# Motor_Control_no_mask.net
KiCad netlist of a schematic drawn in EAGLE
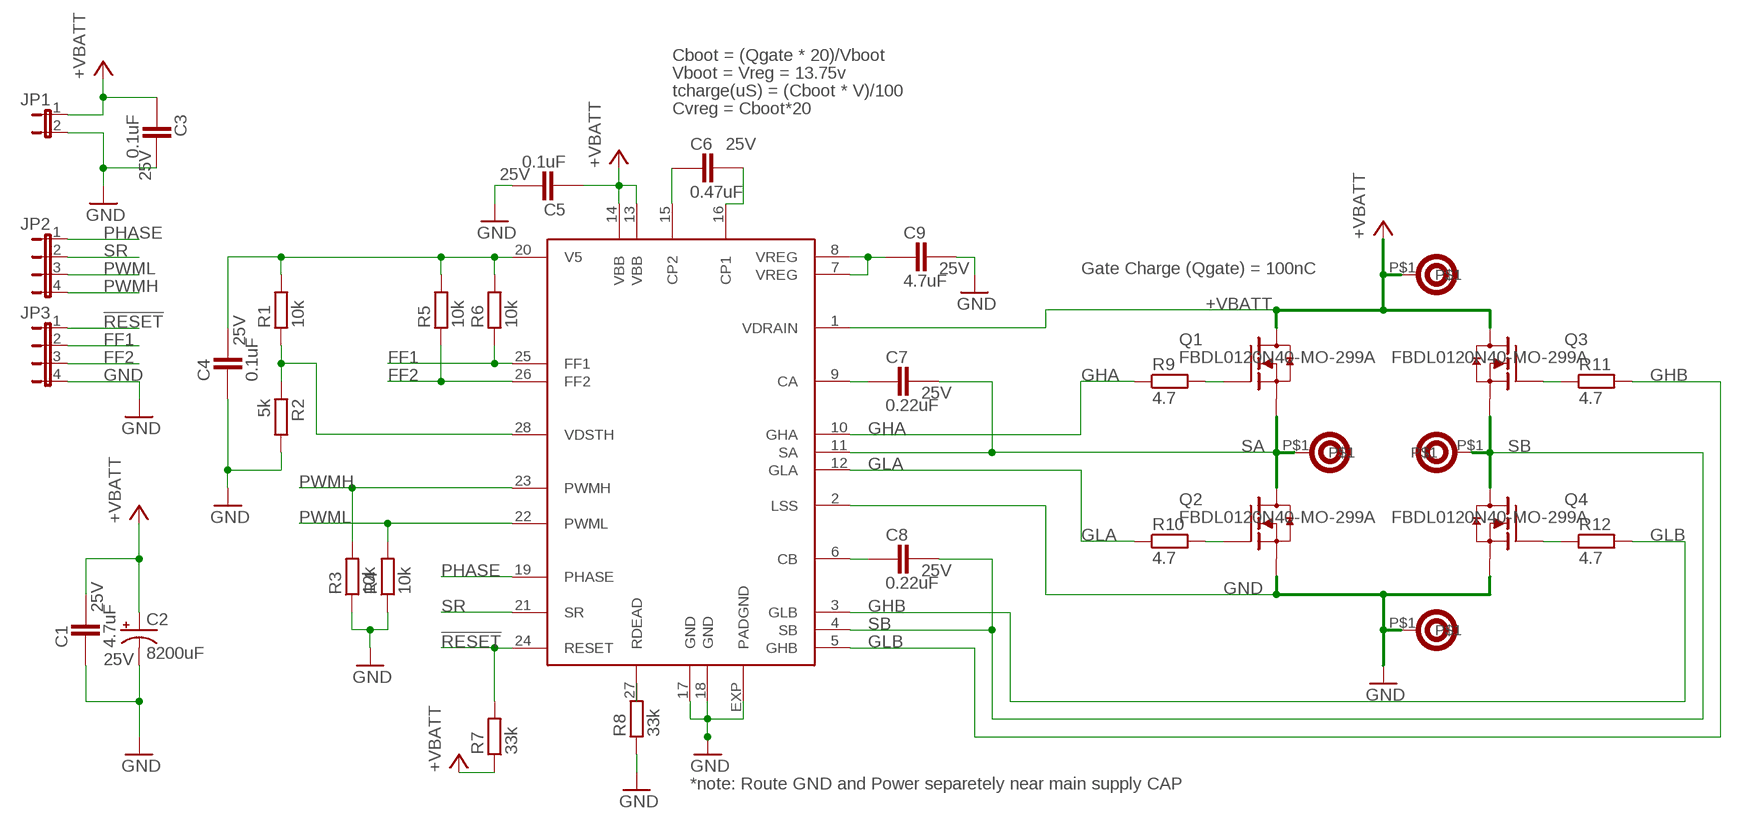
[diagram p0: schematic, sheet 1]

(export (version "E")
  (design (tool "Eeschema 10.0.6"))
  (components
    (comp (ref "C1")
      (value "4.7uF")
      (footprint "eagle-import:CAPC1608X92N")
      (fields (field (name "VOLTAGE") "25V"))
      (libsource (lib "eagle-import") (part "CAPACITOR_0603"))
    )
    (comp (ref "C2")
      (value "8200uF")
      (footprint "eagle-import:CAP-10-22")
      (fields
        (field (name "MANUFACTURER") "Panasonic")
        (field (name "MANUFACTURER_PART_NUMBER") "ECO-S1EA822BA")
        (field (name "VOLTAGE") "25V")
      )
      (libsource (lib "eagle-import") (part "CPOL-US-PTH-10-22"))
    )
    (comp (ref "C3")
      (value "0.1uF")
      (footprint "eagle-import:CAPC1608X92N")
      (fields (field (name "VOLTAGE") "25V"))
      (libsource (lib "eagle-import") (part "CAPACITOR_0603"))
    )
    (comp (ref "C4")
      (value "0.1uF")
      (footprint "eagle-import:CAPC_0603_LONG")
      (fields (field (name "VOLTAGE") "25V"))
      (libsource (lib "eagle-import") (part "CAPACITOR_0603L"))
    )
    (comp (ref "C5")
      (value "0.1uF")
      (footprint "eagle-import:CAPC1608X92N")
      (fields (field (name "VOLTAGE") "25V"))
      (libsource (lib "eagle-import") (part "CAPACITOR_0603"))
    )
    (comp (ref "C6")
      (value "0.47uF")
      (footprint "eagle-import:CAPC1608X92N")
      (fields (field (name "VOLTAGE") "25V"))
      (libsource (lib "eagle-import") (part "CAPACITOR_0603"))
    )
    (comp (ref "C7")
      (value "0.22uF")
      (footprint "eagle-import:CAPC_0603_LONG")
      (fields (field (name "VOLTAGE") "25V"))
      (libsource (lib "eagle-import") (part "CAPACITOR_0603L"))
    )
    (comp (ref "C8")
      (value "0.22uF")
      (footprint "eagle-import:CAPC_0603_LONG")
      (fields (field (name "VOLTAGE") "25V"))
      (libsource (lib "eagle-import") (part "CAPACITOR_0603L"))
    )
    (comp (ref "C9")
      (value "4.7uF")
      (footprint "eagle-import:CAPC1608X92N")
      (fields (field (name "VOLTAGE") "25V"))
      (libsource (lib "eagle-import") (part "CAPACITOR_0603"))
    )
    (comp (ref "J1")
      (value "63971-1-QC_TAB-RA")
      (footprint "eagle-import:QUICK_CONN_TAB-RA")
      (fields
        (field (name "MANUFACTURER") "TE Connectivity")
        (field (name "MANUFACTURER_PART_NUMBER") "63971-1")
      )
      (libsource (lib "eagle-import") (part "63971-1-QC_TAB-RA"))
    )
    (comp (ref "J2")
      (value "63971-1-QC_TAB-RA")
      (footprint "eagle-import:QUICK_CONN_TAB-RA")
      (fields
        (field (name "MANUFACTURER") "TE Connectivity")
        (field (name "MANUFACTURER_PART_NUMBER") "63971-1")
      )
      (libsource (lib "eagle-import") (part "63971-1-QC_TAB-RA"))
    )
    (comp (ref "J3")
      (value "63971-1-QC_TAB-RA")
      (footprint "eagle-import:QUICK_CONN_TAB-RA")
      (fields
        (field (name "MANUFACTURER") "TE Connectivity")
        (field (name "MANUFACTURER_PART_NUMBER") "63971-1")
      )
      (libsource (lib "eagle-import") (part "63971-1-QC_TAB-RA"))
    )
    (comp (ref "J4")
      (value "63971-1-QC_TAB-RA")
      (footprint "eagle-import:QUICK_CONN_TAB-RA")
      (fields
        (field (name "MANUFACTURER") "TE Connectivity")
        (field (name "MANUFACTURER_PART_NUMBER") "63971-1")
      )
      (libsource (lib "eagle-import") (part "63971-1-QC_TAB-RA"))
    )
    (comp (ref "JP1")
      (value "JP1E")
      (footprint "eagle-import:JP1")
      (libsource (lib "eagle-import") (part "JP1E"))
    )
    (comp (ref "JP2")
      (value "JP4E")
      (footprint "eagle-import:JP4")
      (libsource (lib "eagle-import") (part "JP4E"))
    )
    (comp (ref "JP3")
      (value "JP4E")
      (footprint "eagle-import:JP4")
      (libsource (lib "eagle-import") (part "JP4E"))
    )
    (comp (ref "Q1")
      (value "FBDL0120N40-MO-299A")
      (footprint "eagle-import:MO-299")
      (fields
        (field (name "MANUFACTURER") "Fairchild")
        (field (name "MANUFACTURER_PART_NUMBER") "FDBL0120N40")
      )
      (libsource (lib "eagle-import") (part "FBDL0120N40-MO-299A"))
    )
    (comp (ref "Q2")
      (value "FBDL0120N40-MO-299A")
      (footprint "eagle-import:MO-299")
      (fields
        (field (name "MANUFACTURER") "Fairchild")
        (field (name "MANUFACTURER_PART_NUMBER") "FDBL0120N40")
      )
      (libsource (lib "eagle-import") (part "FBDL0120N40-MO-299A"))
    )
    (comp (ref "Q3")
      (value "FBDL0120N40-MO-299A")
      (footprint "eagle-import:MO-299")
      (fields
        (field (name "MANUFACTURER") "Fairchild")
        (field (name "MANUFACTURER_PART_NUMBER") "FDBL0120N40")
      )
      (libsource (lib "eagle-import") (part "FBDL0120N40-MO-299A"))
    )
    (comp (ref "Q4")
      (value "FBDL0120N40-MO-299A")
      (footprint "eagle-import:MO-299")
      (fields
        (field (name "MANUFACTURER") "Fairchild")
        (field (name "MANUFACTURER_PART_NUMBER") "FDBL0120N40")
      )
      (libsource (lib "eagle-import") (part "FBDL0120N40-MO-299A"))
    )
    (comp (ref "R1")
      (value "10k")
      (footprint "eagle-import:RESC1608X55N")
      (libsource (lib "eagle-import") (part "RESISTOR_0603"))
    )
    (comp (ref "R2")
      (value "5k")
      (footprint "eagle-import:RESC1608X55N")
      (libsource (lib "eagle-import") (part "RESISTOR_0603"))
    )
    (comp (ref "R3")
      (value "10k")
      (footprint "eagle-import:RESC1608X55N")
      (libsource (lib "eagle-import") (part "RESISTOR_0603"))
    )
    (comp (ref "R4")
      (value "10k")
      (footprint "eagle-import:RESC1608X55N")
      (libsource (lib "eagle-import") (part "RESISTOR_0603"))
    )
    (comp (ref "R5")
      (value "10k")
      (footprint "eagle-import:RESC1608X55N")
      (libsource (lib "eagle-import") (part "RESISTOR_0603"))
    )
    (comp (ref "R6")
      (value "10k")
      (footprint "eagle-import:RESC1608X55N")
      (libsource (lib "eagle-import") (part "RESISTOR_0603"))
    )
    (comp (ref "R7")
      (value "33k")
      (footprint "eagle-import:RESC1608X55N")
      (libsource (lib "eagle-import") (part "RESISTOR_0603"))
    )
    (comp (ref "R8")
      (value "33k")
      (footprint "eagle-import:RESC1608X55N")
      (libsource (lib "eagle-import") (part "RESISTOR_0603"))
    )
    (comp (ref "R9")
      (value "4.7")
      (footprint "eagle-import:RESC1608X55N")
      (libsource (lib "eagle-import") (part "RESISTOR_0603"))
    )
    (comp (ref "R10")
      (value "4.7")
      (footprint "eagle-import:RESC1608X55N")
      (libsource (lib "eagle-import") (part "RESISTOR_0603"))
    )
    (comp (ref "R11")
      (value "4.7")
      (footprint "eagle-import:RESC1608X55N")
      (libsource (lib "eagle-import") (part "RESISTOR_0603"))
    )
    (comp (ref "R12")
      (value "4.7")
      (footprint "eagle-import:RESC1608X55N")
      (libsource (lib "eagle-import") (part "RESISTOR_0603"))
    )
    (comp (ref "U1")
      (value "A3941-TSSOP28-LP")
      (footprint "eagle-import:TSSOP28-LP")
      (fields
        (field (name "MANUFACTURER") "Allegro MicroSystems LLC")
        (field (name "MANUFACTURER_PART_NUMBER") "A3941")
      )
      (libsource (lib "eagle-import") (part "A3941-TSSOP28-LP"))
    )
  )
  (nets
    (net (code "1") (name "+VBATT") (class "Default")
      (node (ref "C1") (pin "2") (pinfunction "2_2") (pintype "passive"))
      (node (ref "C2") (pin "+") (pinfunction "+_+") (pintype "passive"))
      (node (ref "C3") (pin "1") (pinfunction "1_1") (pintype "passive"))
      (node (ref "C5") (pin "1") (pinfunction "1_1") (pintype "passive"))
      (node (ref "J2") (pin "P$1") (pinfunction "P$1_P$1") (pintype "bidirectional"))
      (node (ref "JP1") (pin "1") (pinfunction "1_1") (pintype "passive"))
      (node (ref "Q1") (pin "P$9") (pinfunction "D_P$9") (pintype "passive"))
      (node (ref "Q3") (pin "P$9") (pinfunction "D_P$9") (pintype "passive"))
      (node (ref "R7") (pin "1") (pinfunction "1_1") (pintype "passive"))
      (node (ref "U1") (pin "1") (pinfunction "VDRAIN_1") (pintype "bidirectional"))
      (node (ref "U1") (pin "13") (pinfunction "VBB_13") (pintype "bidirectional"))
      (node (ref "U1") (pin "14") (pinfunction "VBB_14") (pintype "bidirectional"))
    )
    (net (code "2") (name "/FF1") (class "Default")
      (node (ref "JP3") (pin "2") (pinfunction "2_2") (pintype "passive"))
      (node (ref "R6") (pin "1") (pinfunction "1_1") (pintype "passive"))
      (node (ref "U1") (pin "25") (pinfunction "FF1_25") (pintype "output"))
    )
    (net (code "3") (name "/FF2") (class "Default")
      (node (ref "JP3") (pin "3") (pinfunction "3_3") (pintype "passive"))
      (node (ref "R5") (pin "1") (pinfunction "1_1") (pintype "passive"))
      (node (ref "U1") (pin "26") (pinfunction "FF2_26") (pintype "output"))
    )
    (net (code "4") (name "/GHA") (class "Default")
      (node (ref "R9") (pin "1") (pinfunction "1_1") (pintype "passive"))
      (node (ref "U1") (pin "10") (pinfunction "GHA_10") (pintype "output"))
    )
    (net (code "5") (name "/GHB") (class "Default")
      (node (ref "R11") (pin "2") (pinfunction "2_2") (pintype "passive"))
      (node (ref "U1") (pin "5") (pinfunction "GHB_5") (pintype "output"))
    )
    (net (code "6") (name "/GLA") (class "Default")
      (node (ref "R10") (pin "1") (pinfunction "1_1") (pintype "passive"))
      (node (ref "U1") (pin "12") (pinfunction "GLA_12") (pintype "output"))
    )
    (net (code "7") (name "/GLB") (class "Default")
      (node (ref "R12") (pin "2") (pinfunction "2_2") (pintype "passive"))
      (node (ref "U1") (pin "3") (pinfunction "GLB_3") (pintype "output"))
    )
    (net (code "8") (name "/PHASE") (class "Default")
      (node (ref "JP2") (pin "1") (pinfunction "1_1") (pintype "passive"))
      (node (ref "U1") (pin "19") (pinfunction "PHASE_19") (pintype "input"))
    )
    (net (code "9") (name "/PWMH") (class "Default")
      (node (ref "JP2") (pin "4") (pinfunction "4_4") (pintype "passive"))
      (node (ref "R3") (pin "2") (pinfunction "2_2") (pintype "passive"))
      (node (ref "U1") (pin "23") (pinfunction "PWMH_23") (pintype "input"))
    )
    (net (code "10") (name "/PWML") (class "Default")
      (node (ref "JP2") (pin "3") (pinfunction "3_3") (pintype "passive"))
      (node (ref "R4") (pin "2") (pinfunction "2_2") (pintype "passive"))
      (node (ref "U1") (pin "22") (pinfunction "PWML_22") (pintype "input"))
    )
    (net (code "11") (name "/SA") (class "Default")
      (node (ref "C7") (pin "2") (pinfunction "2_2") (pintype "passive"))
      (node (ref "J1") (pin "P$1") (pinfunction "P$1_P$1") (pintype "bidirectional"))
      (node (ref "Q1") (pin "P$2") (pinfunction "S_P$2") (pintype "passive"))
      (node (ref "Q1") (pin "P$3") (pinfunction "S_P$3") (pintype "passive"))
      (node (ref "Q1") (pin "P$4") (pinfunction "S_P$4") (pintype "passive"))
      (node (ref "Q1") (pin "P$5") (pinfunction "S_P$5") (pintype "passive"))
      (node (ref "Q1") (pin "P$6") (pinfunction "S_P$6") (pintype "passive"))
      (node (ref "Q1") (pin "P$7") (pinfunction "S_P$7") (pintype "passive"))
      (node (ref "Q1") (pin "P$8") (pinfunction "S_P$8") (pintype "passive"))
      (node (ref "Q2") (pin "P$9") (pinfunction "D_P$9") (pintype "passive"))
      (node (ref "U1") (pin "11") (pinfunction "SA_11") (pintype "bidirectional"))
    )
    (net (code "12") (name "/SB") (class "Default")
      (node (ref "C8") (pin "2") (pinfunction "2_2") (pintype "passive"))
      (node (ref "J3") (pin "P$1") (pinfunction "P$1_P$1") (pintype "bidirectional"))
      (node (ref "Q3") (pin "P$2") (pinfunction "S_P$2") (pintype "passive"))
      (node (ref "Q3") (pin "P$3") (pinfunction "S_P$3") (pintype "passive"))
      (node (ref "Q3") (pin "P$4") (pinfunction "S_P$4") (pintype "passive"))
      (node (ref "Q3") (pin "P$5") (pinfunction "S_P$5") (pintype "passive"))
      (node (ref "Q3") (pin "P$6") (pinfunction "S_P$6") (pintype "passive"))
      (node (ref "Q3") (pin "P$7") (pinfunction "S_P$7") (pintype "passive"))
      (node (ref "Q3") (pin "P$8") (pinfunction "S_P$8") (pintype "passive"))
      (node (ref "Q4") (pin "P$9") (pinfunction "D_P$9") (pintype "passive"))
      (node (ref "U1") (pin "4") (pinfunction "SB_4") (pintype "bidirectional"))
    )
    (net (code "13") (name "/SR") (class "Default")
      (node (ref "JP2") (pin "2") (pinfunction "2_2") (pintype "passive"))
      (node (ref "U1") (pin "21") (pinfunction "SR_21") (pintype "input"))
    )
    (net (code "14") (name "/~{RESET}") (class "Default")
      (node (ref "JP3") (pin "1") (pinfunction "1_1") (pintype "passive"))
      (node (ref "R7") (pin "2") (pinfunction "2_2") (pintype "passive"))
      (node (ref "U1") (pin "24") (pinfunction "RESET_24") (pintype "input"))
    )
    (net (code "15") (name "GND") (class "Default")
      (node (ref "C1") (pin "1") (pinfunction "1_1") (pintype "passive"))
      (node (ref "C2") (pin "-") (pinfunction "-_-") (pintype "passive"))
      (node (ref "C3") (pin "2") (pinfunction "2_2") (pintype "passive"))
      (node (ref "C4") (pin "1") (pinfunction "1_1") (pintype "passive"))
      (node (ref "C5") (pin "2") (pinfunction "2_2") (pintype "passive"))
      (node (ref "C9") (pin "2") (pinfunction "2_2") (pintype "passive"))
      (node (ref "J4") (pin "P$1") (pinfunction "P$1_P$1") (pintype "bidirectional"))
      (node (ref "JP1") (pin "2") (pinfunction "2_2") (pintype "passive"))
      (node (ref "JP3") (pin "4") (pinfunction "4_4") (pintype "passive"))
      (node (ref "Q2") (pin "P$2") (pinfunction "S_P$2") (pintype "passive"))
      (node (ref "Q2") (pin "P$3") (pinfunction "S_P$3") (pintype "passive"))
      (node (ref "Q2") (pin "P$4") (pinfunction "S_P$4") (pintype "passive"))
      (node (ref "Q2") (pin "P$5") (pinfunction "S_P$5") (pintype "passive"))
      (node (ref "Q2") (pin "P$6") (pinfunction "S_P$6") (pintype "passive"))
      (node (ref "Q2") (pin "P$7") (pinfunction "S_P$7") (pintype "passive"))
      (node (ref "Q2") (pin "P$8") (pinfunction "S_P$8") (pintype "passive"))
      (node (ref "Q4") (pin "P$2") (pinfunction "S_P$2") (pintype "passive"))
      (node (ref "Q4") (pin "P$3") (pinfunction "S_P$3") (pintype "passive"))
      (node (ref "Q4") (pin "P$4") (pinfunction "S_P$4") (pintype "passive"))
      (node (ref "Q4") (pin "P$5") (pinfunction "S_P$5") (pintype "passive"))
      (node (ref "Q4") (pin "P$6") (pinfunction "S_P$6") (pintype "passive"))
      (node (ref "Q4") (pin "P$7") (pinfunction "S_P$7") (pintype "passive"))
      (node (ref "Q4") (pin "P$8") (pinfunction "S_P$8") (pintype "passive"))
      (node (ref "R2") (pin "2") (pinfunction "2_2") (pintype "passive"))
      (node (ref "R3") (pin "1") (pinfunction "1_1") (pintype "passive"))
      (node (ref "R4") (pin "1") (pinfunction "1_1") (pintype "passive"))
      (node (ref "R8") (pin "1") (pinfunction "1_1") (pintype "passive"))
      (node (ref "U1") (pin "17") (pinfunction "GND_17") (pintype "bidirectional"))
      (node (ref "U1") (pin "18") (pinfunction "GND_18") (pintype "bidirectional"))
      (node (ref "U1") (pin "2") (pinfunction "LSS_2") (pintype "bidirectional"))
      (node (ref "U1") (pin "EXP") (pinfunction "PADGND_EXP") (pintype "bidirectional"))
    )
    (net (code "16") (name "Net-(C9-Pad1)") (class "Default")
      (node (ref "C9") (pin "1") (pinfunction "1_1") (pintype "passive"))
      (node (ref "U1") (pin "7") (pinfunction "VREG_7") (pintype "bidirectional"))
      (node (ref "U1") (pin "8") (pinfunction "VREG_8") (pintype "bidirectional"))
    )
    (net (code "17") (name "Net-(Q1-G)") (class "Default")
      (node (ref "Q1") (pin "P$1") (pinfunction "G_P$1") (pintype "passive"))
      (node (ref "R9") (pin "2") (pinfunction "2_2") (pintype "passive"))
    )
    (net (code "18") (name "Net-(Q2-G)") (class "Default")
      (node (ref "Q2") (pin "P$1") (pinfunction "G_P$1") (pintype "passive"))
      (node (ref "R10") (pin "2") (pinfunction "2_2") (pintype "passive"))
    )
    (net (code "19") (name "Net-(Q3-G)") (class "Default")
      (node (ref "Q3") (pin "P$1") (pinfunction "G_P$1") (pintype "passive"))
      (node (ref "R11") (pin "1") (pinfunction "1_1") (pintype "passive"))
    )
    (net (code "20") (name "Net-(Q4-G)") (class "Default")
      (node (ref "Q4") (pin "P$1") (pinfunction "G_P$1") (pintype "passive"))
      (node (ref "R12") (pin "1") (pinfunction "1_1") (pintype "passive"))
    )
    (net (code "21") (name "Net-(U1-CA)") (class "Default")
      (node (ref "C7") (pin "1") (pinfunction "1_1") (pintype "passive"))
      (node (ref "U1") (pin "9") (pinfunction "CA_9") (pintype "bidirectional"))
    )
    (net (code "22") (name "Net-(U1-CB)") (class "Default")
      (node (ref "C8") (pin "1") (pinfunction "1_1") (pintype "passive"))
      (node (ref "U1") (pin "6") (pinfunction "CB_6") (pintype "bidirectional"))
    )
    (net (code "23") (name "Net-(U1-CP1)") (class "Default")
      (node (ref "C6") (pin "2") (pinfunction "2_2") (pintype "passive"))
      (node (ref "U1") (pin "16") (pinfunction "CP1_16") (pintype "bidirectional"))
    )
    (net (code "24") (name "Net-(U1-CP2)") (class "Default")
      (node (ref "C6") (pin "1") (pinfunction "1_1") (pintype "passive"))
      (node (ref "U1") (pin "15") (pinfunction "CP2_15") (pintype "bidirectional"))
    )
    (net (code "25") (name "Net-(U1-RDEAD)") (class "Default")
      (node (ref "R8") (pin "2") (pinfunction "2_2") (pintype "passive"))
      (node (ref "U1") (pin "27") (pinfunction "RDEAD_27") (pintype "bidirectional"))
    )
    (net (code "26") (name "Net-(U1-V5)") (class "Default")
      (node (ref "C4") (pin "2") (pinfunction "2_2") (pintype "passive"))
      (node (ref "R1") (pin "2") (pinfunction "2_2") (pintype "passive"))
      (node (ref "R5") (pin "2") (pinfunction "2_2") (pintype "passive"))
      (node (ref "R6") (pin "2") (pinfunction "2_2") (pintype "passive"))
      (node (ref "U1") (pin "20") (pinfunction "V5_20") (pintype "bidirectional"))
    )
    (net (code "27") (name "Net-(U1-VDSTH)") (class "Default")
      (node (ref "R1") (pin "1") (pinfunction "1_1") (pintype "passive"))
      (node (ref "R2") (pin "1") (pinfunction "1_1") (pintype "passive"))
      (node (ref "U1") (pin "28") (pinfunction "VDSTH_28") (pintype "input"))
    )
  )
)
